# m2101-psu-dcdc.net
KiCad netlist of a schematic drawn in EAGLE
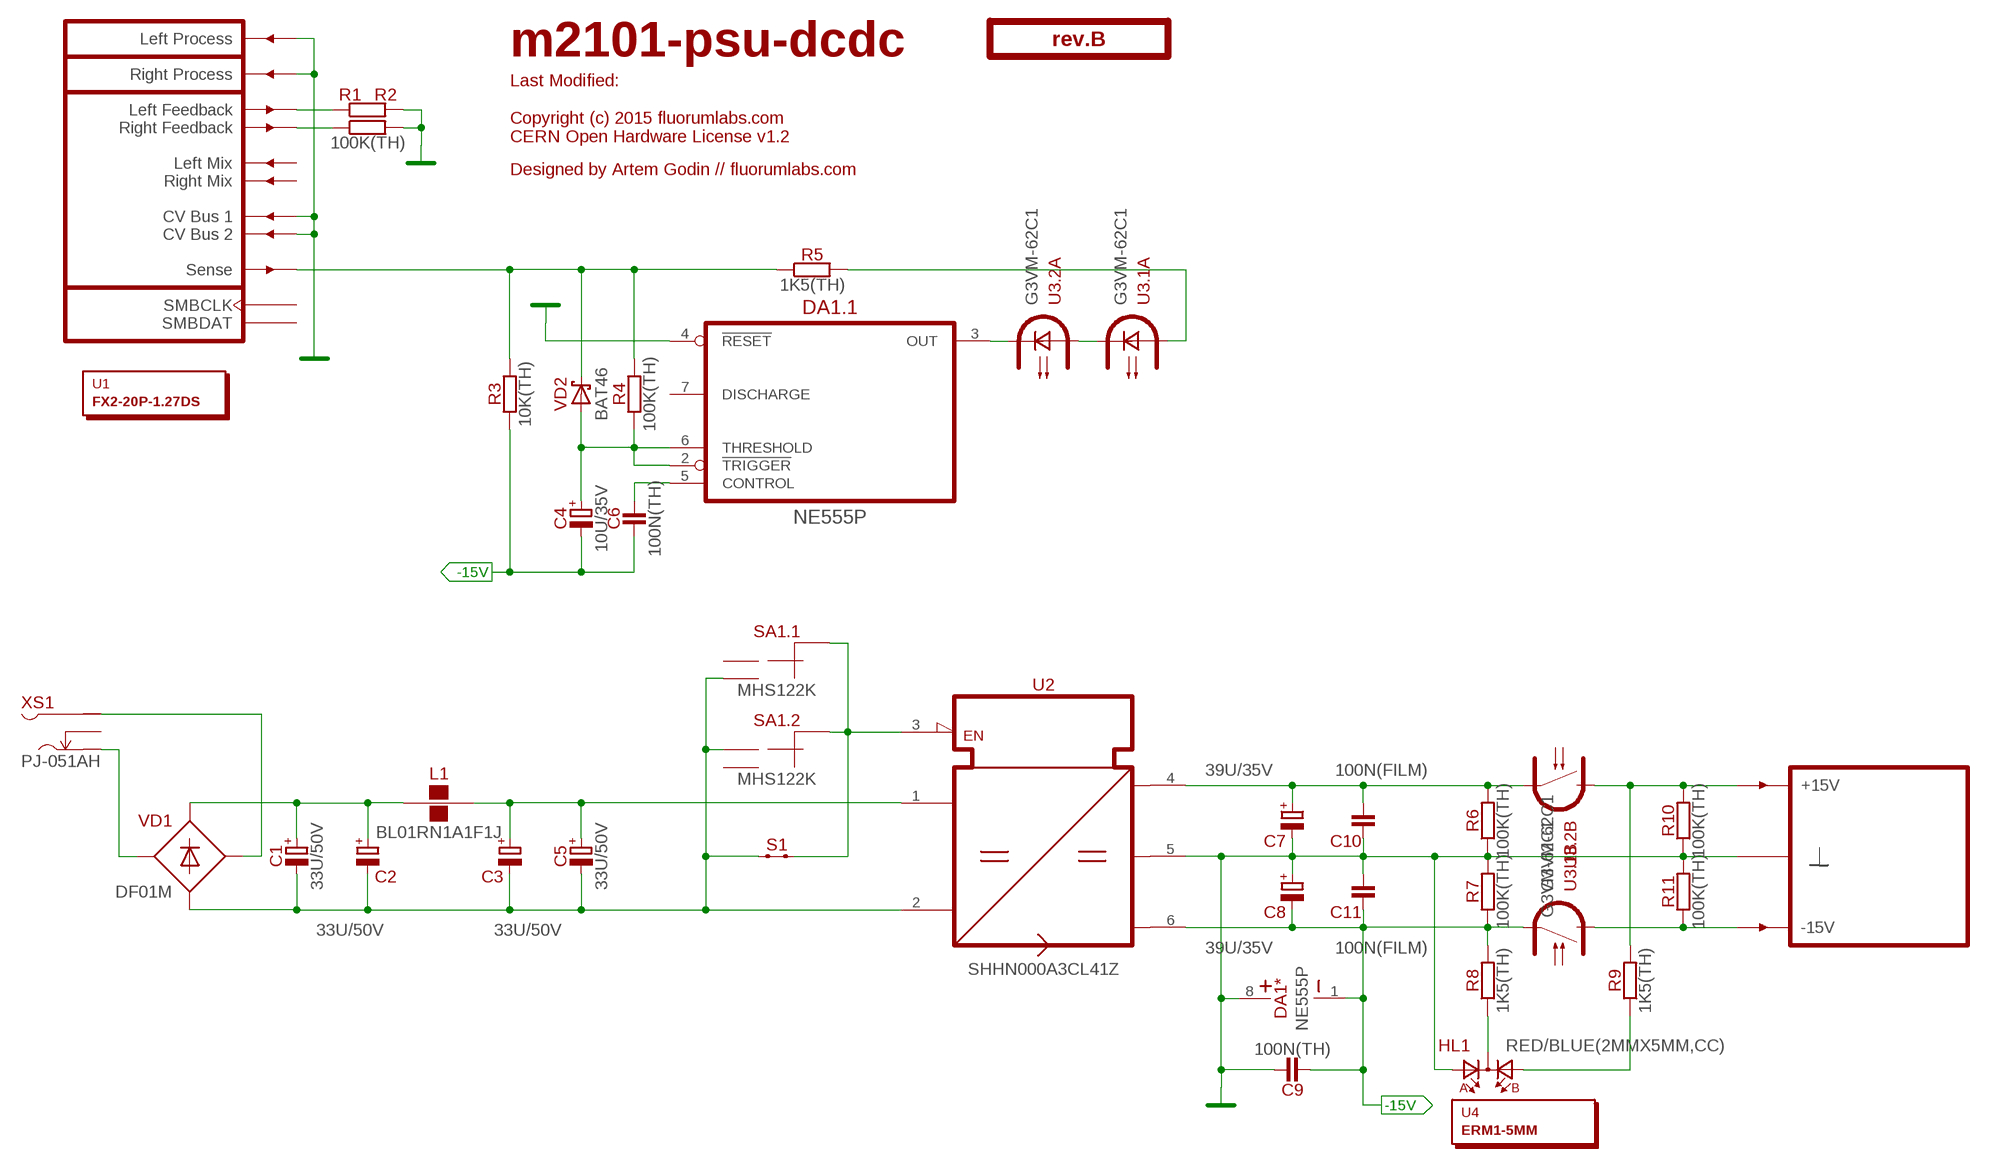
[diagram p0: schematic, sheet 1]

(export (version "E")
  (design (tool "Eeschema 10.0.6"))
  (components
    (comp (ref "C1")
      (value "33U/50V")
      (footprint "eagle-import:E3,5-8")
      (libsource (lib "eagle-import") (part "?33U/50V"))
    )
    (comp (ref "C2")
      (value "33U/50V")
      (footprint "eagle-import:E3,5-8")
      (libsource (lib "eagle-import") (part "?33U/50V"))
    )
    (comp (ref "C3")
      (value "33U/50V")
      (footprint "eagle-import:E3,5-8")
      (libsource (lib "eagle-import") (part "?33U/50V"))
    )
    (comp (ref "C4")
      (value "10U/35V")
      (footprint "eagle-import:E2-5")
      (libsource (lib "eagle-import") (part "?10U/35V"))
    )
    (comp (ref "C5")
      (value "33U/50V")
      (footprint "eagle-import:E3,5-8")
      (libsource (lib "eagle-import") (part "?33U/50V"))
    )
    (comp (ref "C6")
      (value "100N(TH)")
      (footprint "eagle-import:C050-024X044")
      (libsource (lib "eagle-import") (part "?100N(TH)"))
    )
    (comp (ref "C7")
      (value "39U/35V")
      (footprint "eagle-import:E3,5-8")
      (libsource (lib "eagle-import") (part "?39U/35V"))
    )
    (comp (ref "C8")
      (value "39U/35V")
      (footprint "eagle-import:E3,5-8")
      (libsource (lib "eagle-import") (part "?39U/35V"))
    )
    (comp (ref "C9")
      (value "100N(TH)")
      (footprint "eagle-import:C050-024X044")
      (libsource (lib "eagle-import") (part "?100N(TH)"))
    )
    (comp (ref "C10")
      (value "100N(FILM)")
      (footprint "eagle-import:C050-025X075")
      (libsource (lib "eagle-import") (part "?100N(FILM)"))
    )
    (comp (ref "C11")
      (value "100N(FILM)")
      (footprint "eagle-import:C050-025X075")
      (libsource (lib "eagle-import") (part "?100N(FILM)"))
    )
    (comp (ref "DA1")
      (value "NE555P")
      (footprint "eagle-import:DIP-8")
      (libsource (lib "eagle-import") (part "NE555?P"))
    )
    (comp (ref "HL1")
      (value "RED/BLUE(2MMX5MM,CC)")
      (footprint "eagle-import:LED2X5-3PIN")
      (libsource (lib "eagle-import") (part "?(2MMX5MM,CC)RED/BLUE"))
    )
    (comp (ref "L1")
      (value "BL01RN1A1F1J")
      (footprint "eagle-import:BL01RN1A")
      (libsource (lib "eagle-import") (part "BL01RN1A?1F1J"))
    )
    (comp (ref "O1")
      (value "Designed by Artem Godin // fluorumlabs.com")
      (footprint "eagle-import:EMPTY")
      (libsource (lib "eagle-import") (part "TITLE"))
    )
    (comp (ref "PCB1")
      (value "rev.B")
      (footprint "eagle-import:ST2-BOARD-50-PSU")
      (libsource (lib "eagle-import") (part "ST2-BOARD-50-PSU"))
    )
    (comp (ref "R1")
      (value "100K(TH)")
      (footprint "eagle-import:R-0207_10")
      (libsource (lib "eagle-import") (part "?100K(TH)"))
    )
    (comp (ref "R2")
      (value "100K(TH)")
      (footprint "eagle-import:R-0207_10")
      (libsource (lib "eagle-import") (part "?100K(TH)"))
    )
    (comp (ref "R3")
      (value "10K(TH)")
      (footprint "eagle-import:R-0207_10")
      (libsource (lib "eagle-import") (part "?10K(TH)"))
    )
    (comp (ref "R4")
      (value "100K(TH)")
      (footprint "eagle-import:R-0207_10")
      (libsource (lib "eagle-import") (part "?100K(TH)"))
    )
    (comp (ref "R5")
      (value "1K5(TH)")
      (footprint "eagle-import:R-0207_10")
      (libsource (lib "eagle-import") (part "?1K5(TH)"))
    )
    (comp (ref "R6")
      (value "100K(TH)")
      (footprint "eagle-import:R-0207_10")
      (libsource (lib "eagle-import") (part "?100K(TH)"))
    )
    (comp (ref "R7")
      (value "100K(TH)")
      (footprint "eagle-import:R-0207_10")
      (libsource (lib "eagle-import") (part "?100K(TH)"))
    )
    (comp (ref "R8")
      (value "1K5(TH)")
      (footprint "eagle-import:R-0207_10")
      (libsource (lib "eagle-import") (part "?1K5(TH)"))
    )
    (comp (ref "R9")
      (value "1K5(TH)")
      (footprint "eagle-import:R-0207_10")
      (libsource (lib "eagle-import") (part "?1K5(TH)"))
    )
    (comp (ref "R10")
      (value "100K(TH)")
      (footprint "eagle-import:R-0207_10")
      (libsource (lib "eagle-import") (part "?100K(TH)"))
    )
    (comp (ref "R11")
      (value "100K(TH)")
      (footprint "eagle-import:R-0207_10")
      (libsource (lib "eagle-import") (part "?100K(TH)"))
    )
    (comp (ref "S1")
      (value "JUMPER-1POS-SOLDER")
      (footprint "eagle-import:JP1-SOLDER")
      (libsource (lib "eagle-import") (part "JUMPER-1POS-SOLDER"))
    )
    (comp (ref "SA1")
      (value "MHS122K")
      (footprint "eagle-import:APEM-MHS122K")
      (libsource (lib "eagle-import") (part "MHS122K"))
    )
    (comp (ref "U1")
      (value "FX2-20P-1.27DS")
      (footprint "eagle-import:EMPTY")
      (libsource (lib "eagle-import") (part "?FX2-20P-1.27DS"))
    )
    (comp (ref "U2")
      (value "SHHN000A3CL41Z")
      (footprint "eagle-import:DC_DC-C1")
      (libsource (lib "eagle-import") (part "SHHN000A3CL41Z"))
    )
    (comp (ref "U3")
      (value "G3VM-62C1")
      (footprint "eagle-import:DIL08")
      (libsource (lib "eagle-import") (part "G3VM-?2C61"))
    )
    (comp (ref "U4")
      (value "ERM1-5MM")
      (footprint "eagle-import:EMPTY")
      (libsource (lib "eagle-import") (part "?ERM1-5MM"))
    )
    (comp (ref "VD1")
      (value "DF01M")
      (footprint "eagle-import:MDIP-4")
      (libsource (lib "eagle-import") (part "DF?M01"))
    )
    (comp (ref "VD2")
      (value "BAT46")
      (footprint "eagle-import:DO35-7")
      (libsource (lib "eagle-import") (part "?BAT46"))
    )
    (comp (ref "XS1")
      (value "PJ-051AH")
      (footprint "eagle-import:PJ-051AH")
      (libsource (lib "eagle-import") (part "PJ-051?AH"))
    )
  )
  (nets
    (net (code "1") (name "-15V") (class "Default")
      (node (ref "C11") (pin "1") (pinfunction "1_1") (pintype "passive"))
      (node (ref "C4") (pin "-") (pinfunction "-_-") (pintype "passive"))
      (node (ref "C6") (pin "1") (pinfunction "1_1") (pintype "passive"))
      (node (ref "C8") (pin "-") (pinfunction "-_-") (pintype "passive"))
      (node (ref "C9") (pin "1") (pinfunction "1_1") (pintype "passive"))
      (node (ref "DA1") (pin "1") (pinfunction "V-_1") (pintype "power_in"))
      (node (ref "R3") (pin "1") (pinfunction "1_1") (pintype "passive"))
      (node (ref "R7") (pin "1") (pinfunction "1_1") (pintype "passive"))
      (node (ref "R8") (pin "2") (pinfunction "2_2") (pintype "passive"))
      (node (ref "U2") (pin "6") (pinfunction "V-_6") (pintype "power_in"))
      (node (ref "U3") (pin "7") (pinfunction "S2_7") (pintype "passive"))
    )
    (net (code "2") (name "GND") (class "Default")
      (node (ref "C10") (pin "1") (pinfunction "1_1") (pintype "passive"))
      (node (ref "C11") (pin "2") (pinfunction "2_2") (pintype "passive"))
      (node (ref "C7") (pin "-") (pinfunction "-_-") (pintype "passive"))
      (node (ref "C8") (pin "+") (pinfunction "+_+") (pintype "passive"))
      (node (ref "C9") (pin "2") (pinfunction "2_2") (pintype "passive"))
      (node (ref "DA1") (pin "4") (pinfunction "~{RESET}_4") (pintype "input"))
      (node (ref "DA1") (pin "8") (pinfunction "V+_8") (pintype "power_in"))
      (node (ref "HL1") (pin "A1") (pinfunction "A1_A1") (pintype "passive"))
      (node (ref "PCB1") (pin "ACV1'") (pinfunction "CV1'_ACV1'") (pintype "bidirectional"))
      (node (ref "PCB1") (pin "ACV2'") (pinfunction "CV2'_ACV2'") (pintype "bidirectional"))
      (node (ref "PCB1") (pin "B4'") (pinfunction "GND_B4'") (pintype "bidirectional"))
      (node (ref "PCB1") (pin "B5'") (pinfunction "GND_B5'") (pintype "bidirectional"))
      (node (ref "PCB1") (pin "B6'") (pinfunction "GND_B6'") (pintype "bidirectional"))
      (node (ref "PCB1") (pin "B7'") (pinfunction "GND_B7'") (pintype "bidirectional"))
      (node (ref "PCB1") (pin "B8'") (pinfunction "GND_B8'") (pintype "bidirectional"))
      (node (ref "PCB1") (pin "BOUTL'") (pinfunction "OUTL_BOUTL'") (pintype "bidirectional"))
      (node (ref "PCB1") (pin "BOUTR'") (pinfunction "OUTR_BOUTR'") (pintype "bidirectional"))
      (node (ref "R1") (pin "2") (pinfunction "2_2") (pintype "passive"))
      (node (ref "R10") (pin "1") (pinfunction "1_1") (pintype "passive"))
      (node (ref "R11") (pin "2") (pinfunction "2_2") (pintype "passive"))
      (node (ref "R2") (pin "2") (pinfunction "2_2") (pintype "passive"))
      (node (ref "R6") (pin "1") (pinfunction "1_1") (pintype "passive"))
      (node (ref "R7") (pin "2") (pinfunction "2_2") (pintype "passive"))
      (node (ref "U2") (pin "5") (pinfunction "GND_5") (pintype "power_in"))
    )
    (net (code "3") (name "Net-(DA1B-CONTROL)") (class "Default")
      (node (ref "C6") (pin "2") (pinfunction "2_2") (pintype "passive"))
      (node (ref "DA1") (pin "5") (pinfunction "CONTROL_5") (pintype "bidirectional"))
    )
    (net (code "4") (name "Net-(DA1B-OUT)") (class "Default")
      (node (ref "DA1") (pin "3") (pinfunction "OUT_3") (pintype "bidirectional"))
      (node (ref "U3") (pin "4") (pinfunction "C_4") (pintype "passive"))
    )
    (net (code "5") (name "Net-(DA1B-THRESHOLD)") (class "Default")
      (node (ref "C4") (pin "+") (pinfunction "+_+") (pintype "passive"))
      (node (ref "DA1") (pin "2") (pinfunction "~{TRIGGER}_2") (pintype "bidirectional"))
      (node (ref "DA1") (pin "6") (pinfunction "THRESHOLD_6") (pintype "bidirectional"))
      (node (ref "R4") (pin "1") (pinfunction "1_1") (pintype "passive"))
      (node (ref "VD2") (pin "A") (pinfunction "A_A") (pintype "passive"))
    )
    (net (code "6") (name "Net-(HL1-PadA2)") (class "Default")
      (node (ref "HL1") (pin "A2") (pinfunction "A2_A2") (pintype "passive"))
      (node (ref "R9") (pin "1") (pinfunction "1_1") (pintype "passive"))
    )
    (net (code "7") (name "Net-(HL1-PadK)") (class "Default")
      (node (ref "HL1") (pin "K") (pinfunction "K_K") (pintype "passive"))
      (node (ref "R8") (pin "1") (pinfunction "1_1") (pintype "passive"))
    )
    (net (code "8") (name "Net-(PCB1D-LFBK')") (class "Default")
      (node (ref "PCB1") (pin "ALFBK'") (pinfunction "LFBK'_ALFBK'") (pintype "bidirectional"))
      (node (ref "R1") (pin "1") (pinfunction "1_1") (pintype "passive"))
    )
    (net (code "9") (name "Net-(PCB1D-RFBK')") (class "Default")
      (node (ref "PCB1") (pin "ARFBK'") (pinfunction "RFBK'_ARFBK'") (pintype "bidirectional"))
      (node (ref "R2") (pin "1") (pinfunction "1_1") (pintype "passive"))
    )
    (net (code "10") (name "Net-(PCB1D-SENSE')") (class "Default")
      (node (ref "PCB1") (pin "BSENSE'") (pinfunction "SENSE'_BSENSE'") (pintype "bidirectional"))
      (node (ref "R3") (pin "2") (pinfunction "2_2") (pintype "passive"))
      (node (ref "R4") (pin "2") (pinfunction "2_2") (pintype "passive"))
      (node (ref "R5") (pin "1") (pinfunction "1_1") (pintype "passive"))
      (node (ref "VD2") (pin "C") (pinfunction "C_C") (pintype "passive"))
    )
    (net (code "11") (name "Net-(SA1A-CM)") (class "Default")
      (node (ref "S1") (pin "2") (pinfunction "2_2") (pintype "passive"))
      (node (ref "SA1") (pin "CMN") (pinfunction "CM_CMN") (pintype "passive"))
      (node (ref "SA1") (pin "CMN'") (pinfunction "CM_CMN'") (pintype "passive"))
      (node (ref "U2") (pin "3") (pinfunction "EN_3") (pintype "bidirectional"))
    )
    (net (code "12") (name "Net-(SA1B-1)") (class "Default")
      (node (ref "C1") (pin "-") (pinfunction "-_-") (pintype "passive"))
      (node (ref "C2") (pin "-") (pinfunction "-_-") (pintype "passive"))
      (node (ref "C3") (pin "-") (pinfunction "-_-") (pintype "passive"))
      (node (ref "C5") (pin "-") (pinfunction "-_-") (pintype "passive"))
      (node (ref "S1") (pin "1") (pinfunction "1_1") (pintype "passive"))
      (node (ref "SA1") (pin "1'") (pinfunction "1_1'") (pintype "passive"))
      (node (ref "SA1") (pin "2") (pinfunction "2_2") (pintype "passive"))
      (node (ref "U2") (pin "2") (pinfunction "IN-_2") (pintype "power_in"))
      (node (ref "VD1") (pin "4") (pinfunction "A_4") (pintype "passive"))
    )
    (net (code "13") (name "Net-(U2-IN+)") (class "Default")
      (node (ref "C3") (pin "+") (pinfunction "+_+") (pintype "passive"))
      (node (ref "C5") (pin "+") (pinfunction "+_+") (pintype "passive"))
      (node (ref "L1") (pin "2") (pinfunction "2_2") (pintype "passive"))
      (node (ref "U2") (pin "1") (pinfunction "IN+_1") (pintype "power_in"))
    )
    (net (code "14") (name "Net-(U2-V+)") (class "Default")
      (node (ref "C10") (pin "2") (pinfunction "2_2") (pintype "passive"))
      (node (ref "C7") (pin "+") (pinfunction "+_+") (pintype "passive"))
      (node (ref "R6") (pin "2") (pinfunction "2_2") (pintype "passive"))
      (node (ref "U2") (pin "4") (pinfunction "V+_4") (pintype "power_in"))
      (node (ref "U3") (pin "5") (pinfunction "S2_5") (pintype "passive"))
    )
    (net (code "15") (name "Net-(U3A-A)") (class "Default")
      (node (ref "R5") (pin "2") (pinfunction "2_2") (pintype "passive"))
      (node (ref "U3") (pin "1") (pinfunction "A_1") (pintype "passive"))
    )
    (net (code "16") (name "Net-(U3A-C)") (class "Default")
      (node (ref "U3") (pin "2") (pinfunction "C_2") (pintype "passive"))
      (node (ref "U3") (pin "3") (pinfunction "A_3") (pintype "passive"))
    )
    (net (code "17") (name "Net-(U3B-S1)") (class "Default")
      (node (ref "PCB1") (pin "A-15'") (pinfunction "P-15V_A-15'") (pintype "bidirectional"))
      (node (ref "PCB1") (pin "B-15'") (pinfunction "P-15V_B-15'") (pintype "bidirectional"))
      (node (ref "R11") (pin "1") (pinfunction "1_1") (pintype "passive"))
      (node (ref "U3") (pin "8") (pinfunction "S1_8") (pintype "passive"))
    )
    (net (code "18") (name "Net-(U3D-S1)") (class "Default")
      (node (ref "PCB1") (pin "A+15'") (pinfunction "P+15V_A+15'") (pintype "bidirectional"))
      (node (ref "PCB1") (pin "B+15'") (pinfunction "P+15V_B+15'") (pintype "bidirectional"))
      (node (ref "R10") (pin "2") (pinfunction "2_2") (pintype "passive"))
      (node (ref "R9") (pin "2") (pinfunction "2_2") (pintype "passive"))
      (node (ref "U3") (pin "6") (pinfunction "S1_6") (pintype "passive"))
    )
    (net (code "19") (name "Net-(VD1-AC1)") (class "Default")
      (node (ref "VD1") (pin "1") (pinfunction "AC1_1") (pintype "passive"))
      (node (ref "XS1") (pin "3") (pinfunction "S_3") (pintype "passive"))
    )
    (net (code "20") (name "Net-(VD1-AC2)") (class "Default")
      (node (ref "VD1") (pin "2") (pinfunction "AC2_2") (pintype "passive"))
      (node (ref "XS1") (pin "1") (pinfunction "P_1") (pintype "passive"))
    )
    (net (code "21") (name "Net-(VD1-C)") (class "Default")
      (node (ref "C1") (pin "+") (pinfunction "+_+") (pintype "passive"))
      (node (ref "C2") (pin "+") (pinfunction "+_+") (pintype "passive"))
      (node (ref "L1") (pin "1") (pinfunction "1_1") (pintype "passive"))
      (node (ref "VD1") (pin "3") (pinfunction "C_3") (pintype "passive"))
    )
    (net (code "22") (name "unconnected-(DA1B-DISCHARGE-Pad7)") (class "Default")
      (node (ref "DA1") (pin "7") (pinfunction "DISCHARGE_7") (pintype "bidirectional"))
    )
    (net (code "23") (name "unconnected-(PCB1D-LMIX'-PadALMIX')") (class "Default")
      (node (ref "PCB1") (pin "ALMIX'") (pinfunction "LMIX'_ALMIX'") (pintype "bidirectional"))
    )
    (net (code "24") (name "unconnected-(PCB1D-RMIX'-PadARMIX')") (class "Default")
      (node (ref "PCB1") (pin "ARMIX'") (pinfunction "RMIX'_ARMIX'") (pintype "bidirectional"))
    )
    (net (code "25") (name "unconnected-(PCB1E-SMBCLK-PadASMBCLK')") (class "Default")
      (node (ref "PCB1") (pin "ASMBCLK'") (pinfunction "SMBCLK_ASMBCLK'") (pintype "bidirectional"))
    )
    (net (code "26") (name "unconnected-(PCB1E-SMBDAT-PadASMBDAT')") (class "Default")
      (node (ref "PCB1") (pin "ASMBDAT'") (pinfunction "SMBDAT_ASMBDAT'") (pintype "bidirectional"))
    )
    (net (code "27") (name "unconnected-(SA1-Pad1)") (class "Default")
      (node (ref "SA1") (pin "1") (pinfunction "1_1") (pintype "passive"))
    )
    (net (code "28") (name "unconnected-(SA1B-2-Pad2')") (class "Default")
      (node (ref "SA1") (pin "2'") (pinfunction "2_2'") (pintype "passive"))
    )
    (net (code "29") (name "unconnected-(XS1-SS-Pad2)") (class "Default")
      (node (ref "XS1") (pin "2") (pinfunction "SS_2") (pintype "passive"))
    )
  )
)
